# VS1053.net
KiCad netlist of a schematic drawn in Altium Designer
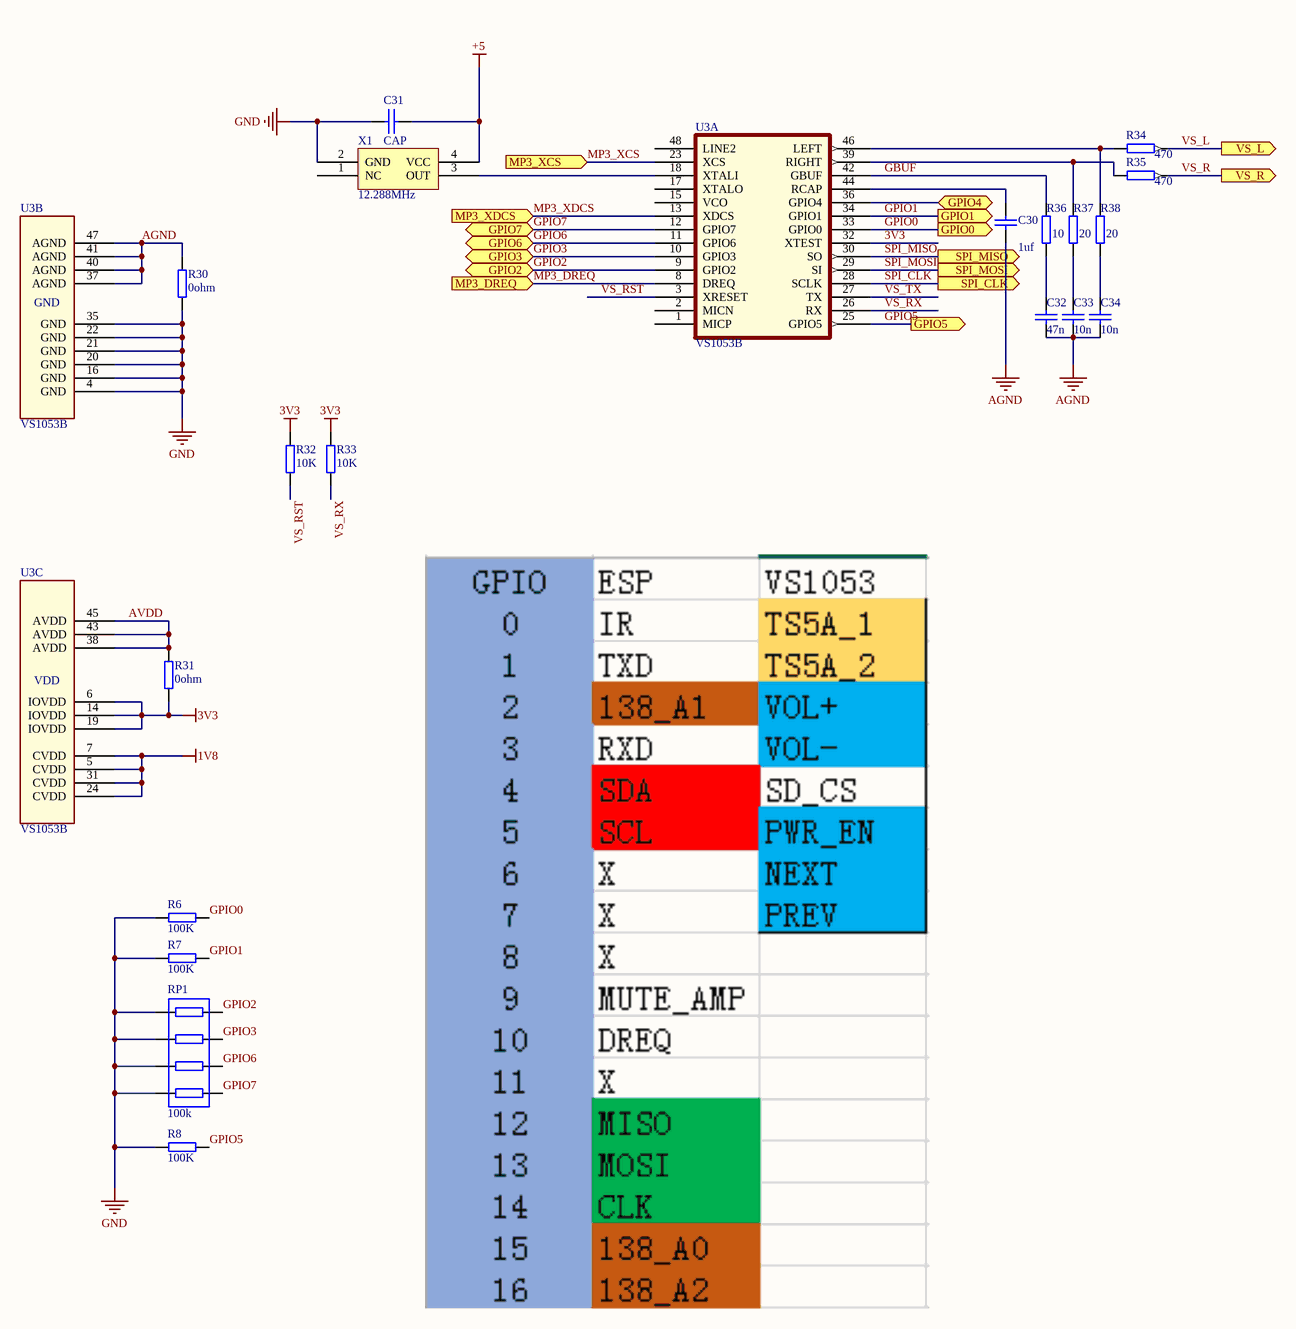
[diagram p0: VS1053.SchDoc]

(export (version "E")
  (design (tool "Eeschema 10.0.6"))
  (components
    (comp (ref "C30")
      (value "1uf")
      (footprint "0402")
      (description "贴片电容")
      (fields (field (name "Comment") "Cap") (field (name "PUBLISHER") "Altium Limited"))
      (libsource (lib "Sparks") (part "Cap"))
    )
    (comp (ref "C31")
      (value "CAP")
      (footprint "3528")
      (description "Capacitor")
      (libsource (lib "9G_SCH") (part "CAP"))
    )
    (comp (ref "C32")
      (value "47n")
      (footprint "0402")
      (description "贴片电容")
      (fields (field (name "PUBLISHER") "Altium Limited"))
      (libsource (lib "Sparks") (part "Cap"))
    )
    (comp (ref "C33")
      (value "10n")
      (footprint "0402")
      (description "贴片电容")
      (fields (field (name "Comment") "Cap") (field (name "PUBLISHER") "Altium Limited"))
      (libsource (lib "Sparks") (part "Cap"))
    )
    (comp (ref "C34")
      (value "10n")
      (footprint "0402")
      (description "贴片电容")
      (fields (field (name "Comment") "Cap") (field (name "PUBLISHER") "Altium Limited"))
      (libsource (lib "Sparks") (part "Cap"))
    )
    (comp (ref "R6")
      (value "100K")
      (footprint "0603AR")
      (description "Resistor")
      (libsource (lib "9G_SCH") (part "RES2"))
    )
    (comp (ref "R7")
      (value "100K")
      (footprint "0603AR")
      (description "Resistor")
      (libsource (lib "9G_SCH") (part "RES2"))
    )
    (comp (ref "R8")
      (value "100K")
      (footprint "0603AR")
      (description "Resistor")
      (libsource (lib "9G_SCH") (part "RES2"))
    )
    (comp (ref "R30")
      (value "0ohm")
      (footprint "0603AC")
      (description "Resistor")
      (libsource (lib "9G_SCH") (part "RES2"))
    )
    (comp (ref "R31")
      (value "0ohm")
      (footprint "0603AC")
      (description "Resistor")
      (libsource (lib "9G_SCH") (part "RES2"))
    )
    (comp (ref "R32")
      (value "10K")
      (footprint "0603AR")
      (description "Resistor")
      (libsource (lib "9G_SCH") (part "RES2"))
    )
    (comp (ref "R33")
      (value "10K")
      (footprint "0603AR")
      (description "Resistor")
      (libsource (lib "9G_SCH") (part "RES2"))
    )
    (comp (ref "R34")
      (value "470")
      (footprint "0603AR")
      (description "Resistor")
      (libsource (lib "9G_SCH") (part "RES2"))
    )
    (comp (ref "R35")
      (value "470")
      (footprint "0603AR")
      (description "Resistor")
      (libsource (lib "9G_SCH") (part "RES2"))
    )
    (comp (ref "R36")
      (value "10")
      (footprint "0603AC")
      (description "Resistor")
      (libsource (lib "9G_SCH") (part "RES2"))
    )
    (comp (ref "R37")
      (value "20")
      (footprint "0603AC")
      (description "Resistor")
      (libsource (lib "9G_SCH") (part "RES2"))
    )
    (comp (ref "R38")
      (value "20")
      (footprint "0603AC")
      (description "Resistor")
      (libsource (lib "9G_SCH") (part "RES2"))
    )
    (comp (ref "RP1")
      (value "100k")
      (footprint "RN8")
      (description "Resistor Network")
      (libsource (lib "9G_SCH") (part "RESPACK4A"))
    )
    (comp (ref "U3") (value "VS1053B") (footprint "LQFP-48") (libsource (lib "") (part "VS1053B_2")))
    (comp (ref "X1")
      (value "12.288MHz")
      (footprint "DIL-14")
      (description "有源晶振")
      (libsource (lib "9G_SCH") (part "OSC"))
    )
  )
  (nets
    (net (code "1") (name "+5") (class "Default")
      (node (ref "C31") (pin "1") (pinfunction "1_1") (pintype "passive"))
      (node (ref "X1") (pin "4") (pinfunction "VCC_4") (pintype "passive"))
    )
    (net (code "2") (name "/AVDD") (class "Default")
      (node (ref "R31") (pin "2") (pinfunction "2_2") (pintype "passive"))
      (node (ref "U3") (pin "38") (pinfunction "AVDD_38") (pintype "passive"))
      (node (ref "U3") (pin "43") (pinfunction "AVDD_43") (pintype "passive"))
      (node (ref "U3") (pin "45") (pinfunction "AVDD_45") (pintype "passive"))
    )
    (net (code "3") (name "/GBUF") (class "Default")
      (node (ref "R36") (pin "1") (pinfunction "1_1") (pintype "passive"))
      (node (ref "U3") (pin "42") (pinfunction "GBUF_42") (pintype "passive"))
    )
    (net (code "4") (name "/GPIO0") (class "Default")
      (node (ref "R6") (pin "2") (pinfunction "2_2") (pintype "passive"))
      (node (ref "U3") (pin "33") (pinfunction "GPIO0_33") (pintype "passive"))
    )
    (net (code "5") (name "/GPIO1") (class "Default")
      (node (ref "R7") (pin "2") (pinfunction "2_2") (pintype "passive"))
      (node (ref "U3") (pin "34") (pinfunction "GPIO1_34") (pintype "passive"))
    )
    (net (code "6") (name "/GPIO2") (class "Default")
      (node (ref "RP1") (pin "8") (pinfunction "8_8") (pintype "passive"))
      (node (ref "U3") (pin "9") (pinfunction "GPIO2_9") (pintype "passive"))
    )
    (net (code "7") (name "/GPIO3") (class "Default")
      (node (ref "RP1") (pin "7") (pinfunction "7_7") (pintype "passive"))
      (node (ref "U3") (pin "10") (pinfunction "GPIO3_10") (pintype "passive"))
    )
    (net (code "8") (name "/GPIO4") (class "Default")
      (node (ref "U3") (pin "36") (pinfunction "GPIO4_36") (pintype "passive"))
    )
    (net (code "9") (name "/GPIO5") (class "Default")
      (node (ref "R8") (pin "2") (pinfunction "2_2") (pintype "passive"))
      (node (ref "U3") (pin "25") (pinfunction "GPIO5_25") (pintype "output"))
    )
    (net (code "10") (name "/GPIO6") (class "Default")
      (node (ref "RP1") (pin "6") (pinfunction "6_6") (pintype "passive"))
      (node (ref "U3") (pin "11") (pinfunction "GPIO6_11") (pintype "passive"))
    )
    (net (code "11") (name "/GPIO7") (class "Default")
      (node (ref "RP1") (pin "5") (pinfunction "5_5") (pintype "passive"))
      (node (ref "U3") (pin "12") (pinfunction "GPIO7_12") (pintype "passive"))
    )
    (net (code "12") (name "/MP3_DREQ") (class "Default")
      (node (ref "U3") (pin "8") (pinfunction "DREQ_8") (pintype "passive"))
    )
    (net (code "13") (name "/MP3_XCS") (class "Default")
      (node (ref "U3") (pin "23") (pinfunction "XCS_23") (pintype "passive"))
    )
    (net (code "14") (name "/MP3_XDCS") (class "Default")
      (node (ref "U3") (pin "13") (pinfunction "XDCS_13") (pintype "passive"))
    )
    (net (code "15") (name "/SPI_CLK") (class "Default")
      (node (ref "U3") (pin "28") (pinfunction "SCLK_28") (pintype "passive"))
    )
    (net (code "16") (name "/SPI_MISO") (class "Default")
      (node (ref "U3") (pin "30") (pinfunction "SO_30") (pintype "output"))
    )
    (net (code "17") (name "/SPI_MOSI") (class "Default")
      (node (ref "U3") (pin "29") (pinfunction "SI_29") (pintype "output"))
    )
    (net (code "18") (name "/VS_L") (class "Default")
      (node (ref "R34") (pin "2") (pinfunction "2_2") (pintype "passive"))
    )
    (net (code "19") (name "/VS_R") (class "Default")
      (node (ref "R35") (pin "2") (pinfunction "2_2") (pintype "passive"))
    )
    (net (code "20") (name "/VS_RST") (class "Default")
      (node (ref "R32") (pin "1") (pinfunction "1_1") (pintype "passive"))
      (node (ref "U3") (pin "3") (pinfunction "XRESET_3") (pintype "passive"))
    )
    (net (code "21") (name "/VS_RX") (class "Default")
      (node (ref "R33") (pin "1") (pinfunction "1_1") (pintype "passive"))
      (node (ref "U3") (pin "26") (pinfunction "RX_26") (pintype "passive"))
    )
    (net (code "22") (name "/VS_TX") (class "Default")
      (node (ref "U3") (pin "27") (pinfunction "TX_27") (pintype "passive"))
    )
    (net (code "23") (name "1V8") (class "Default")
      (node (ref "U3") (pin "24") (pinfunction "CVDD_24") (pintype "passive"))
      (node (ref "U3") (pin "31") (pinfunction "CVDD_31") (pintype "passive"))
      (node (ref "U3") (pin "5") (pinfunction "CVDD_5") (pintype "passive"))
      (node (ref "U3") (pin "7") (pinfunction "CVDD_7") (pintype "passive"))
    )
    (net (code "24") (name "3V3") (class "Default")
      (node (ref "R31") (pin "1") (pinfunction "1_1") (pintype "passive"))
      (node (ref "R32") (pin "2") (pinfunction "2_2") (pintype "passive"))
      (node (ref "R33") (pin "2") (pinfunction "2_2") (pintype "passive"))
      (node (ref "U3") (pin "14") (pinfunction "IOVDD_14") (pintype "passive"))
      (node (ref "U3") (pin "19") (pinfunction "IOVDD_19") (pintype "passive"))
      (node (ref "U3") (pin "32") (pinfunction "XTEST_32") (pintype "passive"))
      (node (ref "U3") (pin "6") (pinfunction "IOVDD_6") (pintype "passive"))
    )
    (net (code "25") (name "AGND") (class "Default")
      (node (ref "C30") (pin "1") (pinfunction "1_1") (pintype "passive"))
      (node (ref "C32") (pin "1") (pinfunction "1_1") (pintype "passive"))
      (node (ref "C33") (pin "1") (pinfunction "1_1") (pintype "passive"))
      (node (ref "C34") (pin "1") (pinfunction "1_1") (pintype "passive"))
      (node (ref "R30") (pin "2") (pinfunction "2_2") (pintype "passive"))
      (node (ref "U3") (pin "37") (pinfunction "AGND_37") (pintype "passive"))
      (node (ref "U3") (pin "40") (pinfunction "AGND_40") (pintype "passive"))
      (node (ref "U3") (pin "41") (pinfunction "AGND_41") (pintype "passive"))
      (node (ref "U3") (pin "47") (pinfunction "AGND_47") (pintype "passive"))
    )
    (net (code "26") (name "GND") (class "Default")
      (node (ref "C31") (pin "2") (pinfunction "2_2") (pintype "passive"))
      (node (ref "R30") (pin "1") (pinfunction "1_1") (pintype "passive"))
      (node (ref "R6") (pin "1") (pinfunction "1_1") (pintype "passive"))
      (node (ref "R7") (pin "1") (pinfunction "1_1") (pintype "passive"))
      (node (ref "R8") (pin "1") (pinfunction "1_1") (pintype "passive"))
      (node (ref "RP1") (pin "1") (pinfunction "1_1") (pintype "passive"))
      (node (ref "RP1") (pin "2") (pinfunction "2_2") (pintype "passive"))
      (node (ref "RP1") (pin "3") (pinfunction "3_3") (pintype "passive"))
      (node (ref "RP1") (pin "4") (pinfunction "4_4") (pintype "passive"))
      (node (ref "U3") (pin "16") (pinfunction "GND_16") (pintype "passive"))
      (node (ref "U3") (pin "20") (pinfunction "GND_20") (pintype "passive"))
      (node (ref "U3") (pin "21") (pinfunction "GND_21") (pintype "passive"))
      (node (ref "U3") (pin "22") (pinfunction "GND_22") (pintype "passive"))
      (node (ref "U3") (pin "35") (pinfunction "GND_35") (pintype "passive"))
      (node (ref "U3") (pin "4") (pinfunction "GND_4") (pintype "passive"))
      (node (ref "X1") (pin "2") (pinfunction "GND_2") (pintype "passive"))
    )
    (net (code "27") (name "Net-(C32-Pad2)") (class "Default")
      (node (ref "C32") (pin "2") (pinfunction "2_2") (pintype "passive"))
      (node (ref "R36") (pin "2") (pinfunction "2_2") (pintype "passive"))
    )
    (net (code "28") (name "Net-(C33-Pad2)") (class "Default")
      (node (ref "C33") (pin "2") (pinfunction "2_2") (pintype "passive"))
      (node (ref "R37") (pin "2") (pinfunction "2_2") (pintype "passive"))
    )
    (net (code "29") (name "Net-(C34-Pad2)") (class "Default")
      (node (ref "C34") (pin "2") (pinfunction "2_2") (pintype "passive"))
      (node (ref "R38") (pin "2") (pinfunction "2_2") (pintype "passive"))
    )
    (net (code "30") (name "Net-(U3A-LEFT)") (class "Default")
      (node (ref "R34") (pin "1") (pinfunction "1_1") (pintype "passive"))
      (node (ref "R38") (pin "1") (pinfunction "1_1") (pintype "passive"))
      (node (ref "U3") (pin "46") (pinfunction "LEFT_46") (pintype "output"))
    )
    (net (code "31") (name "Net-(U3A-RCAP)") (class "Default")
      (node (ref "C30") (pin "2") (pinfunction "2_2") (pintype "passive"))
      (node (ref "U3") (pin "44") (pinfunction "RCAP_44") (pintype "passive"))
    )
    (net (code "32") (name "Net-(U3A-RIGHT)") (class "Default")
      (node (ref "R35") (pin "1") (pinfunction "1_1") (pintype "passive"))
      (node (ref "R37") (pin "1") (pinfunction "1_1") (pintype "passive"))
      (node (ref "U3") (pin "39") (pinfunction "RIGHT_39") (pintype "output"))
    )
    (net (code "33") (name "Net-(U3A-XTALI)") (class "Default")
      (node (ref "U3") (pin "18") (pinfunction "XTALI_18") (pintype "passive"))
      (node (ref "X1") (pin "3") (pinfunction "OUT_3") (pintype "passive"))
    )
    (net (code "34") (name "unconnected-(U3A-LINE2-Pad48)") (class "Default")
      (node (ref "U3") (pin "48") (pinfunction "LINE2_48") (pintype "passive"))
    )
    (net (code "35") (name "unconnected-(U3A-MICN-Pad2)") (class "Default")
      (node (ref "U3") (pin "2") (pinfunction "MICN_2") (pintype "passive"))
    )
    (net (code "36") (name "unconnected-(U3A-MICP-Pad1)") (class "Default")
      (node (ref "U3") (pin "1") (pinfunction "MICP_1") (pintype "passive"))
    )
    (net (code "37") (name "unconnected-(U3A-VCO-Pad15)") (class "Default")
      (node (ref "U3") (pin "15") (pinfunction "VCO_15") (pintype "passive"))
    )
    (net (code "38") (name "unconnected-(U3A-XTALO-Pad17)") (class "Default")
      (node (ref "U3") (pin "17") (pinfunction "XTALO_17") (pintype "passive"))
    )
    (net (code "39") (name "unconnected-(X1-NC-Pad1)") (class "Default")
      (node (ref "X1") (pin "1") (pinfunction "NC_1") (pintype "passive"))
    )
  )
)
